# Truss-Power.net
KiCad netlist of a schematic drawn in EAGLE
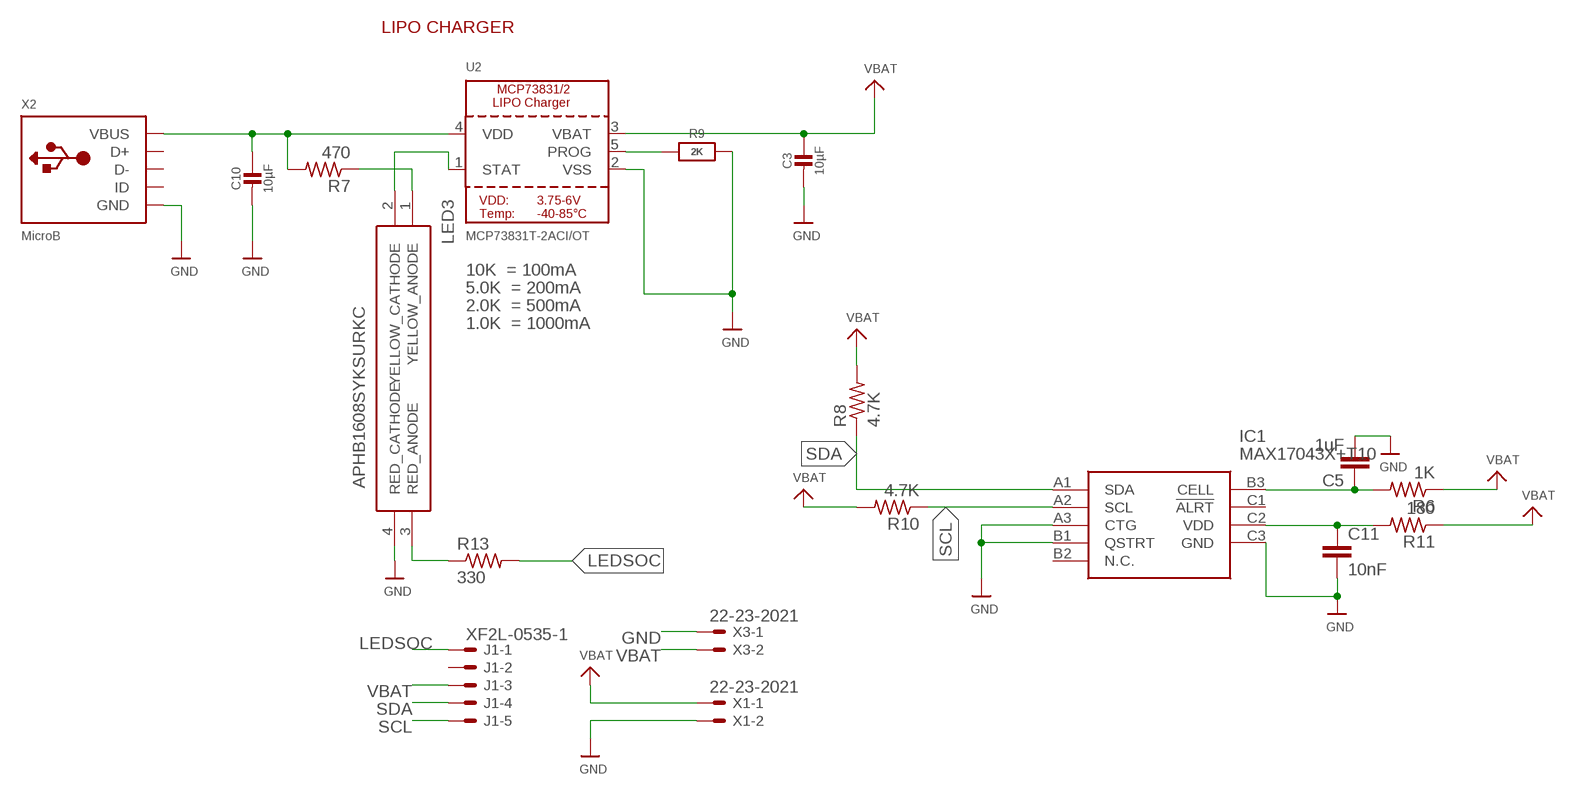
[diagram p0: schematic, sheet 1]

(export (version "E")
  (design (tool "Eeschema 10.0.6"))
  (components
    (comp (ref "C3")
      (value "10µF")
      (footprint "eagle-import:0805-NO")
      (libsource (lib "eagle-import") (part "CAP_CERAMIC0805-NOOUTLINE"))
    )
    (comp (ref "C5")
      (value "1uF")
      (footprint "eagle-import:C0603")
      (libsource (lib "eagle-import") (part "C-EUC0603"))
    )
    (comp (ref "C10")
      (value "10µF")
      (footprint "eagle-import:0805-NO")
      (libsource (lib "eagle-import") (part "CAP_CERAMIC0805-NOOUTLINE"))
    )
    (comp (ref "C11")
      (value "10nF")
      (footprint "eagle-import:C0603")
      (libsource (lib "eagle-import") (part "C-EUC0603"))
    )
    (comp (ref "IC1")
      (value "MAX17043X+T10")
      (footprint "eagle-import:BGA9C40P3X3_160X142X69")
      (fields (field (name "MOUSER_PART_NUMBER") "700-MAX17043X+T10"))
      (libsource (lib "eagle-import") (part "MAX17043X+T10"))
    )
    (comp (ref "J1")
      (value "XF2L-0535-1")
      (footprint "eagle-import:XF2L-0535-1")
      (fields (field (name "MPN") "XF2L-0535-1A"))
      (libsource (lib "eagle-import") (part "XF2-05?35-1L"))
    )
    (comp (ref "LED3")
      (value "APHB1608SYKSURKC")
      (footprint "eagle-import:APHB1608ZGSURKC")
      (fields (field (name "MOUSER_PART_NUMBER") "604-APHB1608SYKSURKC"))
      (libsource (lib "eagle-import") (part "APHB1608SYKSURKC"))
    )
    (comp (ref "R6")
      (value "1K")
      (footprint "eagle-import:R0402")
      (libsource (lib "eagle-import") (part "R-US_R0402"))
    )
    (comp (ref "R7")
      (value "470")
      (footprint "eagle-import:R0402")
      (libsource (lib "eagle-import") (part "R-US_R0402"))
    )
    (comp (ref "R8")
      (value "4.7K")
      (footprint "eagle-import:R0402")
      (libsource (lib "eagle-import") (part "R-US_R0402"))
    )
    (comp (ref "R9")
      (value "2K")
      (footprint "eagle-import:0805-NO")
      (libsource (lib "eagle-import") (part "RESISTOR0805_NOOUTLINE"))
    )
    (comp (ref "R10")
      (value "4.7K")
      (footprint "eagle-import:R0402")
      (libsource (lib "eagle-import") (part "R-US_R0402"))
    )
    (comp (ref "R11")
      (value "180")
      (footprint "eagle-import:R0402")
      (libsource (lib "eagle-import") (part "R-US_R0402"))
    )
    (comp (ref "R13")
      (value "330")
      (footprint "eagle-import:R0402")
      (libsource (lib "eagle-import") (part "R-US_R0402"))
    )
    (comp (ref "U2")
      (value "MCP73831T-2ACI/OT")
      (footprint "eagle-import:SOT23-5")
      (libsource (lib "eagle-import") (part "MCP73831/2"))
    )
    (comp (ref "X1")
      (value "22-23-2021")
      (footprint "eagle-import:22-23-2021")
      (fields (field (name "MF") "MOLEX"))
      (libsource (lib "eagle-import") (part "con-molex_165_22-23-2021"))
    )
    (comp (ref "X2")
      (value "MicroB")
      (footprint "eagle-import:4UCONN_20329")
      (libsource (lib "eagle-import") (part "USBMICRO_20329"))
    )
    (comp (ref "X3")
      (value "22-23-2021")
      (footprint "eagle-import:22-23-2021")
      (fields (field (name "MF") "MOLEX"))
      (libsource (lib "eagle-import") (part "22-23-2021"))
    )
  )
  (nets
    (net (code "1") (name "GND") (class "Default")
      (node (ref "C10") (pin "2") (pinfunction "2_2") (pintype "passive"))
      (node (ref "C11") (pin "2") (pinfunction "2_2") (pintype "passive"))
      (node (ref "C3") (pin "2") (pinfunction "2_2") (pintype "passive"))
      (node (ref "C5") (pin "2") (pinfunction "2_2") (pintype "passive"))
      (node (ref "IC1") (pin "A3") (pinfunction "CTG_A3") (pintype "bidirectional"))
      (node (ref "IC1") (pin "B1") (pinfunction "QSTRT_B1") (pintype "bidirectional"))
      (node (ref "IC1") (pin "C3") (pinfunction "GND_C3") (pintype "bidirectional"))
      (node (ref "LED3") (pin "4") (pinfunction "RED_CATHODE_4") (pintype "bidirectional"))
      (node (ref "R9") (pin "2") (pinfunction "2_2") (pintype "passive"))
      (node (ref "U2") (pin "2") (pinfunction "VSS_2") (pintype "power_in"))
      (node (ref "X1") (pin "2") (pinfunction "S_2") (pintype "passive"))
      (node (ref "X2") (pin "BASE@1") (pinfunction "GND_BASE@1") (pintype "power_in"))
      (node (ref "X2") (pin "BASE@2") (pinfunction "GND_BASE@2") (pintype "power_in"))
      (node (ref "X2") (pin "GND") (pinfunction "GND_GND") (pintype "power_in"))
      (node (ref "X2") (pin "SPRT@1") (pinfunction "GND_SPRT@1") (pintype "power_in"))
      (node (ref "X2") (pin "SPRT@2") (pinfunction "GND_SPRT@2") (pintype "power_in"))
      (node (ref "X2") (pin "SPRT@3") (pinfunction "GND_SPRT@3") (pintype "power_in"))
      (node (ref "X2") (pin "SPRT@4") (pinfunction "GND_SPRT@4") (pintype "power_in"))
      (node (ref "X3") (pin "1") (pinfunction "S_1") (pintype "passive"))
    )
    (net (code "2") (name "LEDSOC") (class "Default")
      (node (ref "J1") (pin "1") (pinfunction "MSV_1") (pintype "passive"))
      (node (ref "R13") (pin "2") (pinfunction "2_2") (pintype "passive"))
    )
    (net (code "3") (name "Net-(IC1-CELL)") (class "Default")
      (node (ref "C5") (pin "1") (pinfunction "1_1") (pintype "passive"))
      (node (ref "IC1") (pin "B3") (pinfunction "CELL_B3") (pintype "bidirectional"))
      (node (ref "R6") (pin "2") (pinfunction "2_2") (pintype "passive"))
    )
    (net (code "4") (name "Net-(IC1-VDD)") (class "Default")
      (node (ref "C11") (pin "1") (pinfunction "1_1") (pintype "passive"))
      (node (ref "IC1") (pin "C2") (pinfunction "VDD_C2") (pintype "bidirectional"))
      (node (ref "R11") (pin "2") (pinfunction "2_2") (pintype "passive"))
    )
    (net (code "5") (name "Net-(LED3-RED_ANODE)") (class "Default")
      (node (ref "LED3") (pin "3") (pinfunction "RED_ANODE_3") (pintype "bidirectional"))
      (node (ref "R13") (pin "1") (pinfunction "1_1") (pintype "passive"))
    )
    (net (code "6") (name "Net-(LED3-YELLOW_ANODE)") (class "Default")
      (node (ref "LED3") (pin "1") (pinfunction "YELLOW_ANODE_1") (pintype "bidirectional"))
      (node (ref "R7") (pin "1") (pinfunction "1_1") (pintype "passive"))
    )
    (net (code "7") (name "Net-(LED3-YELLOW_CATHODE)") (class "Default")
      (node (ref "LED3") (pin "2") (pinfunction "YELLOW_CATHODE_2") (pintype "bidirectional"))
      (node (ref "U2") (pin "1") (pinfunction "STAT_1") (pintype "output"))
    )
    (net (code "8") (name "Net-(U2-PROG)") (class "Default")
      (node (ref "R9") (pin "1") (pinfunction "1_1") (pintype "passive"))
      (node (ref "U2") (pin "5") (pinfunction "PROG_5") (pintype "input"))
    )
    (net (code "9") (name "Net-(U2-VDD)") (class "Default")
      (node (ref "C10") (pin "1") (pinfunction "1_1") (pintype "passive"))
      (node (ref "R7") (pin "2") (pinfunction "2_2") (pintype "passive"))
      (node (ref "U2") (pin "4") (pinfunction "VDD_4") (pintype "power_in"))
      (node (ref "X2") (pin "VBUS") (pinfunction "VBUS_VBUS") (pintype "power_in"))
    )
    (net (code "10") (name "SCL") (class "Default")
      (node (ref "IC1") (pin "A2") (pinfunction "SCL_A2") (pintype "bidirectional"))
      (node (ref "J1") (pin "5") (pinfunction "MS_5") (pintype "passive"))
      (node (ref "R10") (pin "1") (pinfunction "1_1") (pintype "passive"))
    )
    (net (code "11") (name "SDA") (class "Default")
      (node (ref "IC1") (pin "A1") (pinfunction "SDA_A1") (pintype "bidirectional"))
      (node (ref "J1") (pin "4") (pinfunction "MS_4") (pintype "passive"))
      (node (ref "R8") (pin "1") (pinfunction "1_1") (pintype "passive"))
    )
    (net (code "12") (name "VBAT") (class "Default")
      (node (ref "C3") (pin "1") (pinfunction "1_1") (pintype "passive"))
      (node (ref "J1") (pin "3") (pinfunction "MS_3") (pintype "passive"))
      (node (ref "R10") (pin "2") (pinfunction "2_2") (pintype "passive"))
      (node (ref "R11") (pin "1") (pinfunction "1_1") (pintype "passive"))
      (node (ref "R6") (pin "1") (pinfunction "1_1") (pintype "passive"))
      (node (ref "R8") (pin "2") (pinfunction "2_2") (pintype "passive"))
      (node (ref "U2") (pin "3") (pinfunction "VBAT_3") (pintype "power_in"))
      (node (ref "X1") (pin "1") (pinfunction "S_1") (pintype "passive"))
      (node (ref "X3") (pin "2") (pinfunction "S_2") (pintype "passive"))
    )
    (net (code "13") (name "unconnected-(IC1-N.C.-PadB2)") (class "Default")
      (node (ref "IC1") (pin "B2") (pinfunction "N.C._B2") (pintype "no_connect"))
    )
    (net (code "14") (name "unconnected-(IC1-~{ALRT}-PadC1)") (class "Default")
      (node (ref "IC1") (pin "C1") (pinfunction "~{ALRT}_C1") (pintype "bidirectional"))
    )
    (net (code "15") (name "unconnected-(J1B-MS-Pad2)") (class "Default")
      (node (ref "J1") (pin "2") (pinfunction "MS_2") (pintype "passive"))
    )
    (net (code "16") (name "unconnected-(X2-PadD+)") (class "Default")
      (node (ref "X2") (pin "D+") (pinfunction "D+_D+") (pintype "bidirectional"))
    )
    (net (code "17") (name "unconnected-(X2-PadD-)") (class "Default")
      (node (ref "X2") (pin "D-") (pinfunction "D-_D-") (pintype "bidirectional"))
    )
    (net (code "18") (name "unconnected-(X2-PadID)") (class "Default")
      (node (ref "X2") (pin "ID") (pinfunction "ID_ID") (pintype "bidirectional"))
    )
  )
)
